# design.net
KiCad netlist of a schematic drawn in Altium Designer
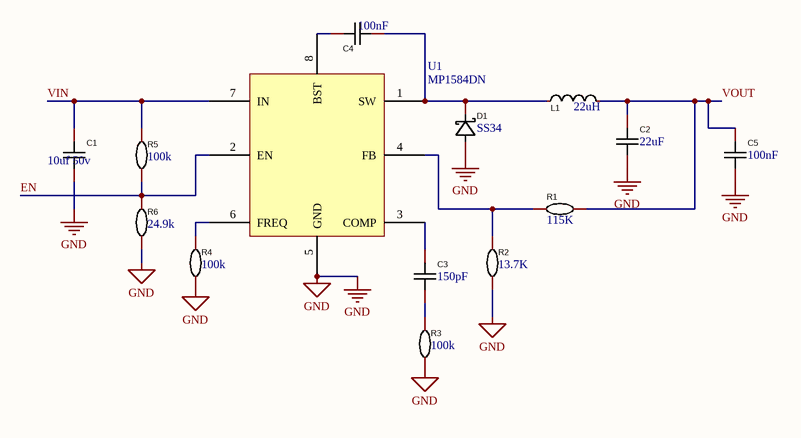
[diagram p0: 降压模块.SchDoc]

(export (version "E")
  (design (tool "Eeschema 10.0.6"))
  (components
    (comp (ref "C1")
      (value "10uf 50v")
      (footprint "C1206")
      (description "型号： CGA5L1X7R0J226MT0Y0E\r\n品牌： TDK\r\n封装： 1206\r\n描述：容值：22uF 精度：±20% 额定电压：6.3V 材质(温度系数)：X7R")
      (fields (field (name "MANUFACTURER") "TDK") (field (name "MANUFACTURER PART") "CGA5L1X7R0J226MT0Y0E"))
      (libsource (lib "降压模块") (part "电容22uf 6.3v x7r"))
    )
    (comp (ref "C2")
      (value "22uF")
      (footprint "C1206")
      (description "1206")
      (fields (field (name "MANUFACTURER") "TDK") (field (name "MANUFACTURER PART") "CGA5L1X7R0J226MT0Y0E"))
      (libsource (lib "降压模块") (part "电容22uf 6.3v x7r"))
    )
    (comp (ref "C3")
      (value "150pF")
      (footprint "R0603")
      (description "型号： CGA5L1X7R0J226MT0Y0E\r\n品牌： TDK\r\n封装： 1206\r\n描述：容值：22uF 精度：±20% 额定电压：6.3V 材质(温度系数)：X7R")
      (fields (field (name "MANUFACTURER") "TDK") (field (name "MANUFACTURER PART") "CGA5L1X7R0J226MT0Y0E"))
      (libsource (lib "降压模块") (part "电容22uf 6.3v x7r"))
    )
    (comp (ref "C4")
      (value "100nF")
      (footprint "R0603")
      (description "型号： CGA5L1X7R0J226MT0Y0E\r\n品牌： TDK\r\n封装： 1206\r\n描述：容值：22uF 精度：±20% 额定电压：6.3V 材质(温度系数)：X7R")
      (fields (field (name "MANUFACTURER") "TDK") (field (name "MANUFACTURER PART") "CGA5L1X7R0J226MT0Y0E"))
      (libsource (lib "降压模块") (part "电容22uf 6.3v x7r"))
    )
    (comp (ref "C5")
      (value "100nF")
      (footprint "R0603")
      (description "型号： CGA5L1X7R0J226MT0Y0E\r\n品牌： TDK\r\n封装： 1206\r\n描述：容值：22uF 精度：±20% 额定电压：6.3V 材质(温度系数)：X7R")
      (fields (field (name "MANUFACTURER") "TDK") (field (name "MANUFACTURER PART") "CGA5L1X7R0J226MT0Y0E"))
      (libsource (lib "降压模块") (part "电容22uf 6.3v x7r"))
    )
    (comp (ref "D1")
      (value "SS34")
      (footprint "ss34  SMA_L4.3-W2.5-LS5.0-RD")
      (fields (field (name "MANUFACTURER") "TWGMC(台湾迪嘉)"))
      (libsource (lib "降压模块") (part "SS34"))
    )
    (comp (ref "L1")
      (value "22uH")
      (footprint "功率电感15uh")
      (description "能装上就行")
      (fields
        (field (name "MANUFACTURER") "Sunlord(顺络)")
        (field (name "MANUFACTURER PART") "MWSA1004S-150MT")
      )
      (libsource (lib "降压模块") (part "功率电感 15uh"))
    )
    (comp (ref "R1")
      (value "115K")
      (footprint "R0603")
      (fields
        (field (name "MANUFACTURER") "FH(风华)")
        (field (name "MANUFACTURER PART") "RS-03K2103FT")
        (field (name "TOLERANCE") "±1%")
      )
      (libsource (lib "降压模块") (part "res"))
    )
    (comp (ref "R2")
      (value "13.7K")
      (footprint "R0603")
      (fields
        (field (name "MANUFACTURER") "FH(风华)")
        (field (name "MANUFACTURER PART") "RS-03K2103FT")
        (field (name "TOLERANCE") "±1%")
      )
      (libsource (lib "降压模块") (part "res"))
    )
    (comp (ref "R3")
      (value "100k")
      (footprint "R0603")
      (fields
        (field (name "MANUFACTURER") "FH(风华)")
        (field (name "MANUFACTURER PART") "RS-03K2103FT")
        (field (name "TOLERANCE") "±1%")
      )
      (libsource (lib "降压模块") (part "res"))
    )
    (comp (ref "R4")
      (value "100k")
      (footprint "R0603")
      (fields
        (field (name "MANUFACTURER") "FH(风华)")
        (field (name "MANUFACTURER PART") "RS-03K2103FT")
        (field (name "TOLERANCE") "±1%")
      )
      (libsource (lib "降压模块") (part "res"))
    )
    (comp (ref "R5")
      (value "100k")
      (footprint "R0603")
      (fields
        (field (name "MANUFACTURER") "FH(风华)")
        (field (name "MANUFACTURER PART") "RS-03K2103FT")
        (field (name "TOLERANCE") "±1%")
      )
      (libsource (lib "降压模块") (part "res"))
    )
    (comp (ref "R6")
      (value "24.9k")
      (footprint "R0603")
      (fields
        (field (name "MANUFACTURER") "FH(风华)")
        (field (name "MANUFACTURER PART") "RS-03K2103FT")
        (field (name "TOLERANCE") "±1%")
      )
      (libsource (lib "降压模块") (part "res"))
    )
    (comp (ref "U1")
      (value "MP1584DN")
      (footprint "LC-SOIC-8_EP_150mil")
      (libsource (lib "降压模块") (part "MP1584DN"))
    )
  )
  (nets
    (net (code "1") (name "/EN") (class "Default")
      (node (ref "R5") (pin "1") (pinfunction "1_1") (pintype "passive"))
      (node (ref "R6") (pin "2") (pinfunction "2_2") (pintype "passive"))
      (node (ref "U1") (pin "2") (pinfunction "EN_2") (pintype "passive"))
    )
    (net (code "2") (name "/VIN") (class "Default")
      (node (ref "C1") (pin "2") (pinfunction "2_2") (pintype "passive"))
      (node (ref "R5") (pin "2") (pinfunction "2_2") (pintype "passive"))
      (node (ref "U1") (pin "7") (pinfunction "IN_7") (pintype "passive"))
    )
    (net (code "3") (name "/VOUT") (class "Default")
      (node (ref "C2") (pin "2") (pinfunction "2_2") (pintype "passive"))
      (node (ref "C5") (pin "2") (pinfunction "2_2") (pintype "passive"))
      (node (ref "L1") (pin "2") (pinfunction "2_2") (pintype "passive"))
      (node (ref "R1") (pin "1") (pinfunction "1_1") (pintype "passive"))
    )
    (net (code "4") (name "GND") (class "Default")
      (node (ref "C1") (pin "1") (pinfunction "1_1") (pintype "passive"))
      (node (ref "C2") (pin "1") (pinfunction "1_1") (pintype "passive"))
      (node (ref "C5") (pin "1") (pinfunction "1_1") (pintype "passive"))
      (node (ref "D1") (pin "2") (pinfunction "A_2") (pintype "passive"))
      (node (ref "R2") (pin "1") (pinfunction "1_1") (pintype "passive"))
      (node (ref "R3") (pin "1") (pinfunction "1_1") (pintype "passive"))
      (node (ref "R4") (pin "1") (pinfunction "1_1") (pintype "passive"))
      (node (ref "R6") (pin "1") (pinfunction "1_1") (pintype "passive"))
      (node (ref "U1") (pin "5") (pinfunction "GND_5") (pintype "passive"))
    )
    (net (code "5") (name "Net-(C3-Pad1)") (class "Default")
      (node (ref "C3") (pin "1") (pinfunction "1_1") (pintype "passive"))
      (node (ref "R3") (pin "2") (pinfunction "2_2") (pintype "passive"))
    )
    (net (code "6") (name "Net-(D1-C)") (class "Default")
      (node (ref "C4") (pin "2") (pinfunction "2_2") (pintype "passive"))
      (node (ref "D1") (pin "1") (pinfunction "C_1") (pintype "passive"))
      (node (ref "L1") (pin "1") (pinfunction "1_1") (pintype "passive"))
      (node (ref "U1") (pin "1") (pinfunction "SW_1") (pintype "passive"))
    )
    (net (code "7") (name "Net-(U1-BST)") (class "Default")
      (node (ref "C4") (pin "1") (pinfunction "1_1") (pintype "passive"))
      (node (ref "U1") (pin "8") (pinfunction "BST_8") (pintype "passive"))
    )
    (net (code "8") (name "Net-(U1-COMP)") (class "Default")
      (node (ref "C3") (pin "2") (pinfunction "2_2") (pintype "passive"))
      (node (ref "U1") (pin "3") (pinfunction "COMP_3") (pintype "passive"))
    )
    (net (code "9") (name "Net-(U1-FB)") (class "Default")
      (node (ref "R1") (pin "2") (pinfunction "2_2") (pintype "passive"))
      (node (ref "R2") (pin "2") (pinfunction "2_2") (pintype "passive"))
      (node (ref "U1") (pin "4") (pinfunction "FB_4") (pintype "passive"))
    )
    (net (code "10") (name "Net-(U1-FREQ)") (class "Default")
      (node (ref "R4") (pin "2") (pinfunction "2_2") (pintype "passive"))
      (node (ref "U1") (pin "6") (pinfunction "FREQ_6") (pintype "passive"))
    )
  )
)
